# FAJAS_V2.net
KiCad netlist of a schematic drawn in EAGLE
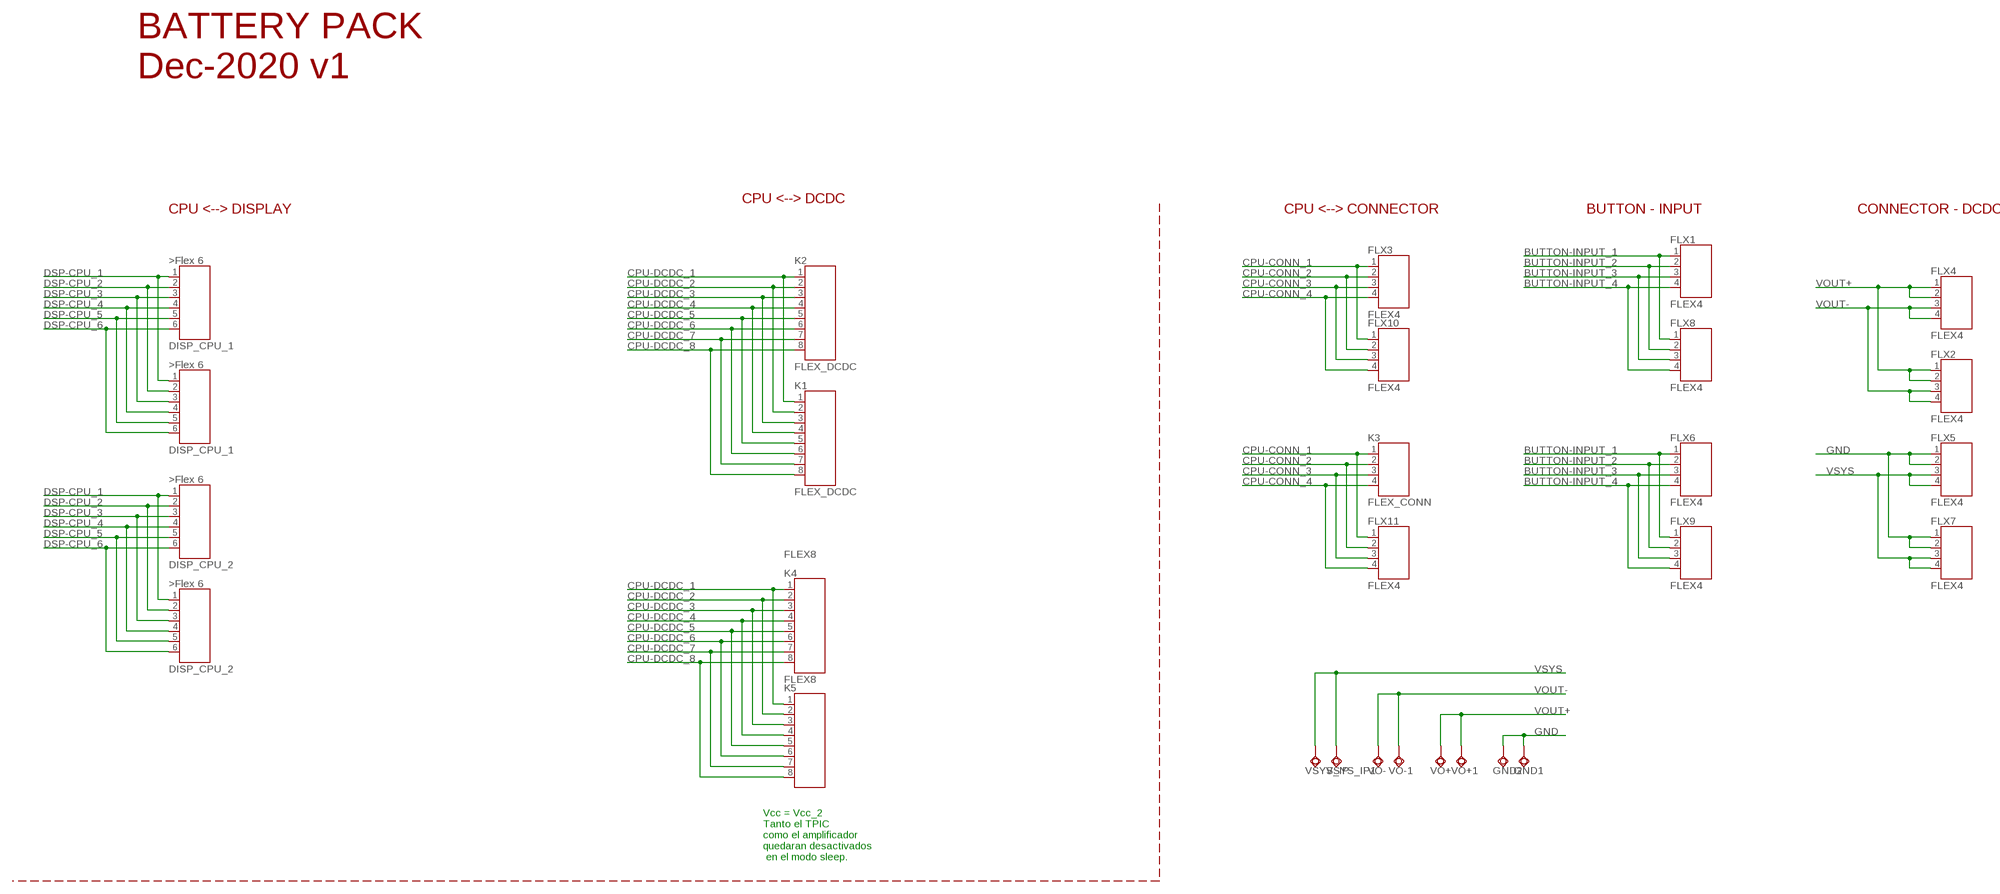
[diagram p0: schematic, sheet 1]

(export (version "E")
  (design (tool "Eeschema 10.0.6"))
  (components
    (comp (ref "DISP_CPU_1")
      (value "DISP_CPU_1")
      (footprint "eagle-import:FLEX6")
      (libsource (lib "eagle-import") (part "FLEX6"))
    )
    (comp (ref "DISP_CPU_2")
      (value "DISP_CPU_2")
      (footprint "eagle-import:FLEX6")
      (libsource (lib "eagle-import") (part "FLEX6"))
    )
    (comp (ref "DISP_CPU_3")
      (value "DISP_CPU_2")
      (footprint "eagle-import:FLEX6")
      (libsource (lib "eagle-import") (part "FLEX6"))
    )
    (comp (ref "DISP_CPU_4")
      (value "DISP_CPU_1")
      (footprint "eagle-import:FLEX6")
      (libsource (lib "eagle-import") (part "FLEX6"))
    )
    (comp (ref "FLX1")
      (value "FLEX4")
      (footprint "eagle-import:FLEX4")
      (libsource (lib "eagle-import") (part "FLEX4"))
    )
    (comp (ref "FLX2")
      (value "FLEX4")
      (footprint "eagle-import:FLEX4")
      (libsource (lib "eagle-import") (part "FLEX4"))
    )
    (comp (ref "FLX3")
      (value "FLEX4")
      (footprint "eagle-import:FLEX4")
      (libsource (lib "eagle-import") (part "FLEX4"))
    )
    (comp (ref "FLX4")
      (value "FLEX4")
      (footprint "eagle-import:FLEX4")
      (libsource (lib "eagle-import") (part "FLEX4"))
    )
    (comp (ref "FLX5")
      (value "FLEX4")
      (footprint "eagle-import:FLEX4")
      (libsource (lib "eagle-import") (part "FLEX4"))
    )
    (comp (ref "FLX6")
      (value "FLEX4")
      (footprint "eagle-import:FLEX4")
      (libsource (lib "eagle-import") (part "FLEX4"))
    )
    (comp (ref "FLX7")
      (value "FLEX4")
      (footprint "eagle-import:FLEX4")
      (libsource (lib "eagle-import") (part "FLEX4"))
    )
    (comp (ref "FLX8")
      (value "FLEX4")
      (footprint "eagle-import:FLEX4")
      (libsource (lib "eagle-import") (part "FLEX4"))
    )
    (comp (ref "FLX9")
      (value "FLEX4")
      (footprint "eagle-import:FLEX4")
      (libsource (lib "eagle-import") (part "FLEX4"))
    )
    (comp (ref "FLX10")
      (value "FLEX4")
      (footprint "eagle-import:FLEX4")
      (libsource (lib "eagle-import") (part "FLEX4"))
    )
    (comp (ref "FLX11")
      (value "FLEX4")
      (footprint "eagle-import:FLEX4")
      (libsource (lib "eagle-import") (part "FLEX4"))
    )
    (comp (ref "GND1")
      (value "TESTPAD_TPSQTP15SQ")
      (footprint "eagle-import:TESTPAD_TP15SQ")
      (libsource (lib "eagle-import") (part "TESTPAD_TPSQTP15SQ"))
    )
    (comp (ref "GND2")
      (value "TESTPAD_TPSQTP15SQ")
      (footprint "eagle-import:TESTPAD_TP15SQ")
      (libsource (lib "eagle-import") (part "TESTPAD_TPSQTP15SQ"))
    )
    (comp (ref "K1")
      (value "FLEX_DCDC")
      (footprint "eagle-import:FLEX8")
      (libsource (lib "eagle-import") (part "FLEX8"))
    )
    (comp (ref "K2")
      (value "FLEX_DCDC")
      (footprint "eagle-import:FLEX8")
      (libsource (lib "eagle-import") (part "FLEX8"))
    )
    (comp (ref "K3")
      (value "FLEX_CONN")
      (footprint "eagle-import:FLEX4")
      (libsource (lib "eagle-import") (part "FLEX4"))
    )
    (comp (ref "K4")
      (value "FLEX8")
      (footprint "eagle-import:FLEX8")
      (libsource (lib "eagle-import") (part "FLEX8"))
    )
    (comp (ref "K5")
      (value "FLEX8")
      (footprint "eagle-import:FLEX8")
      (libsource (lib "eagle-import") (part "FLEX8"))
    )
    (comp (ref "VO+")
      (value "TESTPAD_TPSQTP15SQ")
      (footprint "eagle-import:TESTPAD_TP15SQ")
      (libsource (lib "eagle-import") (part "TESTPAD_TPSQTP15SQ"))
    )
    (comp (ref "VO+1")
      (value "TESTPAD_TPSQTP15SQ")
      (footprint "eagle-import:TESTPAD_TP15SQ")
      (libsource (lib "eagle-import") (part "TESTPAD_TPSQTP15SQ"))
    )
    (comp (ref "VO-")
      (value "TESTPAD_TPSQTP15SQ")
      (footprint "eagle-import:TESTPAD_TP15SQ")
      (libsource (lib "eagle-import") (part "TESTPAD_TPSQTP15SQ"))
    )
    (comp (ref "VO-1")
      (value "TESTPAD_TPSQTP15SQ")
      (footprint "eagle-import:TESTPAD_TP15SQ")
      (libsource (lib "eagle-import") (part "TESTPAD_TPSQTP15SQ"))
    )
    (comp (ref "VSYS_IP")
      (value "TESTPAD_TPSQTP15SQ")
      (footprint "eagle-import:TESTPAD_TP15SQ")
      (libsource (lib "eagle-import") (part "TESTPAD_TPSQTP15SQ"))
    )
    (comp (ref "VSYS_IP1")
      (value "TESTPAD_TPSQTP15SQ")
      (footprint "eagle-import:TESTPAD_TP15SQ")
      (libsource (lib "eagle-import") (part "TESTPAD_TPSQTP15SQ"))
    )
  )
  (nets
    (net (code "1") (name "/BUTTON-INPUT_1") (class "Default")
      (node (ref "FLX1") (pin "1") (pinfunction "1_1") (pintype "passive"))
      (node (ref "FLX6") (pin "1") (pinfunction "1_1") (pintype "passive"))
      (node (ref "FLX8") (pin "1") (pinfunction "1_1") (pintype "passive"))
      (node (ref "FLX9") (pin "1") (pinfunction "1_1") (pintype "passive"))
    )
    (net (code "2") (name "/BUTTON-INPUT_2") (class "Default")
      (node (ref "FLX1") (pin "2") (pinfunction "2_2") (pintype "passive"))
      (node (ref "FLX6") (pin "2") (pinfunction "2_2") (pintype "passive"))
      (node (ref "FLX8") (pin "2") (pinfunction "2_2") (pintype "passive"))
      (node (ref "FLX9") (pin "2") (pinfunction "2_2") (pintype "passive"))
    )
    (net (code "3") (name "/BUTTON-INPUT_3") (class "Default")
      (node (ref "FLX1") (pin "3") (pinfunction "3_3") (pintype "passive"))
      (node (ref "FLX6") (pin "3") (pinfunction "3_3") (pintype "passive"))
      (node (ref "FLX8") (pin "3") (pinfunction "3_3") (pintype "passive"))
      (node (ref "FLX9") (pin "3") (pinfunction "3_3") (pintype "passive"))
    )
    (net (code "4") (name "/BUTTON-INPUT_4") (class "Default")
      (node (ref "FLX1") (pin "4") (pinfunction "4_4") (pintype "passive"))
      (node (ref "FLX6") (pin "4") (pinfunction "4_4") (pintype "passive"))
      (node (ref "FLX8") (pin "4") (pinfunction "4_4") (pintype "passive"))
      (node (ref "FLX9") (pin "4") (pinfunction "4_4") (pintype "passive"))
    )
    (net (code "5") (name "/CPU-CONN_1") (class "Default")
      (node (ref "FLX10") (pin "1") (pinfunction "1_1") (pintype "passive"))
      (node (ref "FLX11") (pin "1") (pinfunction "1_1") (pintype "passive"))
      (node (ref "FLX3") (pin "1") (pinfunction "1_1") (pintype "passive"))
      (node (ref "K3") (pin "1") (pinfunction "1_1") (pintype "passive"))
    )
    (net (code "6") (name "/CPU-CONN_2") (class "Default")
      (node (ref "FLX10") (pin "2") (pinfunction "2_2") (pintype "passive"))
      (node (ref "FLX11") (pin "2") (pinfunction "2_2") (pintype "passive"))
      (node (ref "FLX3") (pin "2") (pinfunction "2_2") (pintype "passive"))
      (node (ref "K3") (pin "2") (pinfunction "2_2") (pintype "passive"))
    )
    (net (code "7") (name "/CPU-CONN_3") (class "Default")
      (node (ref "FLX10") (pin "3") (pinfunction "3_3") (pintype "passive"))
      (node (ref "FLX11") (pin "3") (pinfunction "3_3") (pintype "passive"))
      (node (ref "FLX3") (pin "3") (pinfunction "3_3") (pintype "passive"))
      (node (ref "K3") (pin "3") (pinfunction "3_3") (pintype "passive"))
    )
    (net (code "8") (name "/CPU-CONN_4") (class "Default")
      (node (ref "FLX10") (pin "4") (pinfunction "4_4") (pintype "passive"))
      (node (ref "FLX11") (pin "4") (pinfunction "4_4") (pintype "passive"))
      (node (ref "FLX3") (pin "4") (pinfunction "4_4") (pintype "passive"))
      (node (ref "K3") (pin "4") (pinfunction "4_4") (pintype "passive"))
    )
    (net (code "9") (name "/CPU-DCDC_1") (class "Default")
      (node (ref "K1") (pin "1") (pinfunction "1_1") (pintype "passive"))
      (node (ref "K2") (pin "1") (pinfunction "1_1") (pintype "passive"))
      (node (ref "K4") (pin "1") (pinfunction "1_1") (pintype "passive"))
      (node (ref "K5") (pin "1") (pinfunction "1_1") (pintype "passive"))
    )
    (net (code "10") (name "/CPU-DCDC_2") (class "Default")
      (node (ref "K1") (pin "2") (pinfunction "2_2") (pintype "passive"))
      (node (ref "K2") (pin "2") (pinfunction "2_2") (pintype "passive"))
      (node (ref "K4") (pin "2") (pinfunction "2_2") (pintype "passive"))
      (node (ref "K5") (pin "2") (pinfunction "2_2") (pintype "passive"))
    )
    (net (code "11") (name "/CPU-DCDC_3") (class "Default")
      (node (ref "K1") (pin "3") (pinfunction "3_3") (pintype "passive"))
      (node (ref "K2") (pin "3") (pinfunction "3_3") (pintype "passive"))
      (node (ref "K4") (pin "3") (pinfunction "3_3") (pintype "passive"))
      (node (ref "K5") (pin "3") (pinfunction "3_3") (pintype "passive"))
    )
    (net (code "12") (name "/CPU-DCDC_4") (class "Default")
      (node (ref "K1") (pin "4") (pinfunction "4_4") (pintype "passive"))
      (node (ref "K2") (pin "4") (pinfunction "4_4") (pintype "passive"))
      (node (ref "K4") (pin "4") (pinfunction "4_4") (pintype "passive"))
      (node (ref "K5") (pin "4") (pinfunction "4_4") (pintype "passive"))
    )
    (net (code "13") (name "/CPU-DCDC_5") (class "Default")
      (node (ref "K1") (pin "5") (pinfunction "5_5") (pintype "passive"))
      (node (ref "K2") (pin "5") (pinfunction "5_5") (pintype "passive"))
      (node (ref "K4") (pin "5") (pinfunction "5_5") (pintype "passive"))
      (node (ref "K5") (pin "5") (pinfunction "5_5") (pintype "passive"))
    )
    (net (code "14") (name "/CPU-DCDC_6") (class "Default")
      (node (ref "K1") (pin "6") (pinfunction "6_6") (pintype "passive"))
      (node (ref "K2") (pin "6") (pinfunction "6_6") (pintype "passive"))
      (node (ref "K4") (pin "6") (pinfunction "6_6") (pintype "passive"))
      (node (ref "K5") (pin "6") (pinfunction "6_6") (pintype "passive"))
    )
    (net (code "15") (name "/CPU-DCDC_7") (class "Default")
      (node (ref "K1") (pin "7") (pinfunction "7_7") (pintype "passive"))
      (node (ref "K2") (pin "7") (pinfunction "7_7") (pintype "passive"))
      (node (ref "K4") (pin "7") (pinfunction "7_7") (pintype "passive"))
      (node (ref "K5") (pin "7") (pinfunction "7_7") (pintype "passive"))
    )
    (net (code "16") (name "/CPU-DCDC_8") (class "Default")
      (node (ref "K1") (pin "8") (pinfunction "8_8") (pintype "passive"))
      (node (ref "K2") (pin "8") (pinfunction "8_8") (pintype "passive"))
      (node (ref "K4") (pin "8") (pinfunction "8_8") (pintype "passive"))
      (node (ref "K5") (pin "8") (pinfunction "8_8") (pintype "passive"))
    )
    (net (code "17") (name "/DSP-CPU_1") (class "Default")
      (node (ref "DISP_CPU_1") (pin "1") (pinfunction "1_1") (pintype "passive"))
      (node (ref "DISP_CPU_2") (pin "1") (pinfunction "1_1") (pintype "passive"))
      (node (ref "DISP_CPU_3") (pin "1") (pinfunction "1_1") (pintype "passive"))
      (node (ref "DISP_CPU_4") (pin "1") (pinfunction "1_1") (pintype "passive"))
    )
    (net (code "18") (name "/DSP-CPU_2") (class "Default")
      (node (ref "DISP_CPU_1") (pin "2") (pinfunction "2_2") (pintype "passive"))
      (node (ref "DISP_CPU_2") (pin "2") (pinfunction "2_2") (pintype "passive"))
      (node (ref "DISP_CPU_3") (pin "2") (pinfunction "2_2") (pintype "passive"))
      (node (ref "DISP_CPU_4") (pin "2") (pinfunction "2_2") (pintype "passive"))
    )
    (net (code "19") (name "/DSP-CPU_3") (class "Default")
      (node (ref "DISP_CPU_1") (pin "3") (pinfunction "3_3") (pintype "passive"))
      (node (ref "DISP_CPU_2") (pin "3") (pinfunction "3_3") (pintype "passive"))
      (node (ref "DISP_CPU_3") (pin "3") (pinfunction "3_3") (pintype "passive"))
      (node (ref "DISP_CPU_4") (pin "3") (pinfunction "3_3") (pintype "passive"))
    )
    (net (code "20") (name "/DSP-CPU_4") (class "Default")
      (node (ref "DISP_CPU_1") (pin "4") (pinfunction "4_4") (pintype "passive"))
      (node (ref "DISP_CPU_2") (pin "4") (pinfunction "4_4") (pintype "passive"))
      (node (ref "DISP_CPU_3") (pin "4") (pinfunction "4_4") (pintype "passive"))
      (node (ref "DISP_CPU_4") (pin "4") (pinfunction "4_4") (pintype "passive"))
    )
    (net (code "21") (name "/DSP-CPU_5") (class "Default")
      (node (ref "DISP_CPU_1") (pin "5") (pinfunction "5_5") (pintype "passive"))
      (node (ref "DISP_CPU_2") (pin "5") (pinfunction "5_5") (pintype "passive"))
      (node (ref "DISP_CPU_3") (pin "5") (pinfunction "5_5") (pintype "passive"))
      (node (ref "DISP_CPU_4") (pin "5") (pinfunction "5_5") (pintype "passive"))
    )
    (net (code "22") (name "/DSP-CPU_6") (class "Default")
      (node (ref "DISP_CPU_1") (pin "6") (pinfunction "6_6") (pintype "passive"))
      (node (ref "DISP_CPU_2") (pin "6") (pinfunction "6_6") (pintype "passive"))
      (node (ref "DISP_CPU_3") (pin "6") (pinfunction "6_6") (pintype "passive"))
      (node (ref "DISP_CPU_4") (pin "6") (pinfunction "6_6") (pintype "passive"))
    )
    (net (code "23") (name "/GND") (class "Default")
      (node (ref "FLX5") (pin "1") (pinfunction "1_1") (pintype "passive"))
      (node (ref "FLX5") (pin "2") (pinfunction "2_2") (pintype "passive"))
      (node (ref "FLX7") (pin "1") (pinfunction "1_1") (pintype "passive"))
      (node (ref "FLX7") (pin "2") (pinfunction "2_2") (pintype "passive"))
      (node (ref "GND1") (pin "TP") (pinfunction "TP_TP") (pintype "input"))
      (node (ref "GND2") (pin "TP") (pinfunction "TP_TP") (pintype "input"))
    )
    (net (code "24") (name "/VOUT+") (class "Default")
      (node (ref "FLX2") (pin "1") (pinfunction "1_1") (pintype "passive"))
      (node (ref "FLX2") (pin "2") (pinfunction "2_2") (pintype "passive"))
      (node (ref "FLX4") (pin "1") (pinfunction "1_1") (pintype "passive"))
      (node (ref "FLX4") (pin "2") (pinfunction "2_2") (pintype "passive"))
      (node (ref "VO+") (pin "TP") (pinfunction "TP_TP") (pintype "input"))
      (node (ref "VO+1") (pin "TP") (pinfunction "TP_TP") (pintype "input"))
    )
    (net (code "25") (name "/VOUT-") (class "Default")
      (node (ref "FLX2") (pin "3") (pinfunction "3_3") (pintype "passive"))
      (node (ref "FLX2") (pin "4") (pinfunction "4_4") (pintype "passive"))
      (node (ref "FLX4") (pin "3") (pinfunction "3_3") (pintype "passive"))
      (node (ref "FLX4") (pin "4") (pinfunction "4_4") (pintype "passive"))
      (node (ref "VO-") (pin "TP") (pinfunction "TP_TP") (pintype "input"))
      (node (ref "VO-1") (pin "TP") (pinfunction "TP_TP") (pintype "input"))
    )
    (net (code "26") (name "/VSYS") (class "Default")
      (node (ref "FLX5") (pin "3") (pinfunction "3_3") (pintype "passive"))
      (node (ref "FLX5") (pin "4") (pinfunction "4_4") (pintype "passive"))
      (node (ref "FLX7") (pin "3") (pinfunction "3_3") (pintype "passive"))
      (node (ref "FLX7") (pin "4") (pinfunction "4_4") (pintype "passive"))
      (node (ref "VSYS_IP") (pin "TP") (pinfunction "TP_TP") (pintype "input"))
      (node (ref "VSYS_IP1") (pin "TP") (pinfunction "TP_TP") (pintype "input"))
    )
  )
)
